# POWER.net
KiCad netlist of a schematic drawn in Altium Designer
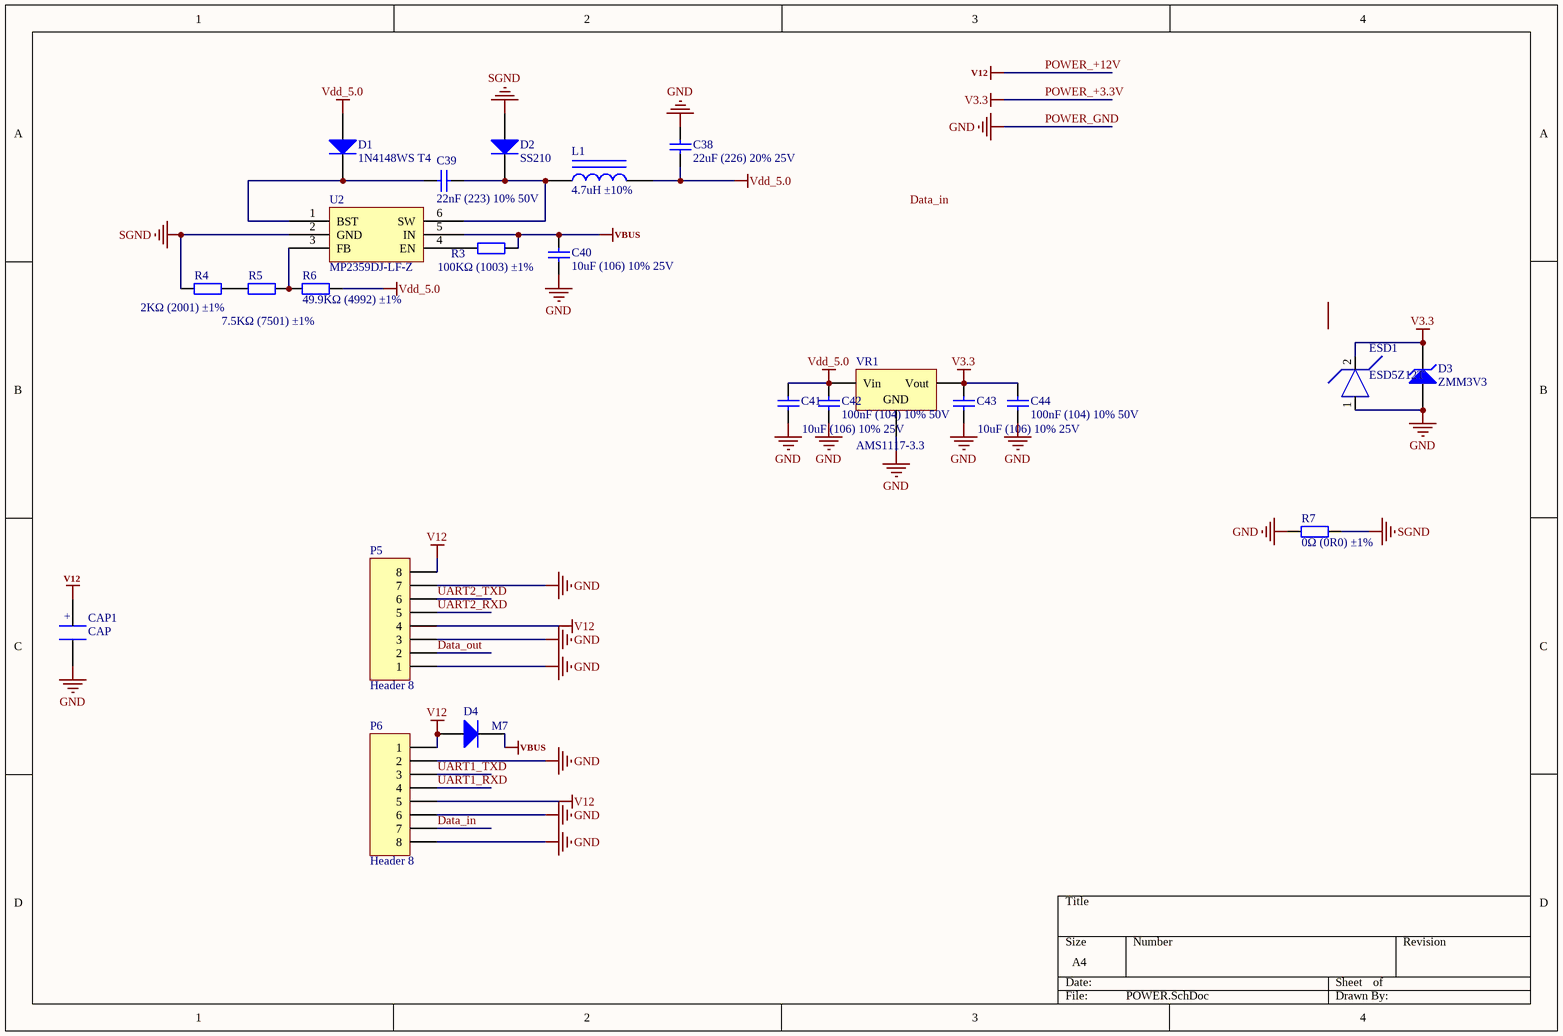
[diagram p0: POWER.SchDoc]

(export (version "E")
  (design (tool "Eeschema 10.0.6"))
  (components
    (comp (ref "C38")
      (value "22uF (226) 20% 25V")
      (footprint "0805_C")
      (description "贴片电容")
      (libsource (lib "Miscellaneous Devices LC") (part "0805 22uF (226) 20% 25V"))
    )
    (comp (ref "C39")
      (value "22nF (223) 10% 50V")
      (footprint "0603_C")
      (description "贴片电容")
      (libsource (lib "Miscellaneous Devices LC") (part "0603 22nF (223) 10% 50V"))
    )
    (comp (ref "C40")
      (value "10uF (106) 10% 25V")
      (footprint "0805_C")
      (description "贴片电容")
      (libsource (lib "Miscellaneous Devices LC") (part "0805 10uF (106) 10% 25V"))
    )
    (comp (ref "C41")
      (value "10uF (106) 10% 25V")
      (footprint "0805_C")
      (description "贴片电容")
      (libsource (lib "Miscellaneous Devices LC") (part "0805 10uF (106) 10% 25V"))
    )
    (comp (ref "C42")
      (value "100nF (104) 10% 50V")
      (footprint "0603_C")
      (description "贴片电容")
      (libsource (lib "Miscellaneous Devices LC") (part "0603 100nF (104) 10% 50V"))
    )
    (comp (ref "C43")
      (value "10uF (106) 10% 25V")
      (footprint "0805_C")
      (description "贴片电容")
      (libsource (lib "Miscellaneous Devices LC") (part "0805 10uF (106) 10% 25V"))
    )
    (comp (ref "C44")
      (value "100nF (104) 10% 50V")
      (footprint "0603_C")
      (description "贴片电容")
      (libsource (lib "Miscellaneous Devices LC") (part "0603 100nF (104) 10% 50V"))
    )
    (comp (ref "CAP1") (value "CAP") (footprint "8X12_CAP") (libsource (lib "mylib") (part "CAP")))
    (comp (ref "D1")
      (value "1N4148WS T4")
      (footprint "SOD-323")
      (description "二极管")
      (libsource (lib "Miscellaneous Devices LC") (part "SOD-323 1N4148WS T4"))
    )
    (comp (ref "D2")
      (value "SS210")
      (footprint "SMA(DO-214AC)_S1")
      (description "二极管")
      (libsource (lib "Miscellaneous Devices LC") (part "SMA(DO-214AC) SS210"))
    )
    (comp (ref "D3")
      (value "ZMM3V3")
      (footprint "LL-34")
      (description "稳压二极管")
      (libsource (lib "Miscellaneous Devices LC") (part "LL-34 ZMM3V3"))
    )
    (comp (ref "D4")
      (value "M7")
      (footprint "SMA(DO-214AC)_S1")
      (description "二极管")
      (libsource (lib "Miscellaneous Devices LC") (part "SMA(DO-214AC) M7"))
    )
    (comp (ref "ESD1") (value "ESD5Z12T") (footprint "SOD-523") (libsource (lib "mylib") (part "ESD-D")))
    (comp (ref "L1")
      (value "4.7uH ±10%")
      (footprint "L_4030")
      (description "贴片电感")
      (libsource (lib "Miscellaneous Devices LC") (part "0603 4.7uH 10%"))
    )
    (comp (ref "P5")
      (value "Header 8")
      (footprint "FPC1.0-2H-WS-8P")
      (description "Header, 8-Pin")
      (fields (field (name "PUBLISHER") "Altium Limited"))
      (libsource (lib "Miscellaneous Connectors") (part "Header 8"))
    )
    (comp (ref "P6")
      (value "Header 8")
      (footprint "FPC1.0-2H-WS-8P")
      (description "Header, 8-Pin")
      (fields (field (name "PUBLISHER") "Altium Limited"))
      (libsource (lib "") (part "Header 8_1"))
    )
    (comp (ref "R3")
      (value "100KΩ (1003) ±1%")
      (footprint "0603_R")
      (description "贴片电阻")
      (libsource (lib "Miscellaneous Devices LC") (part "0603 100KΩ (1003) 1%"))
    )
    (comp (ref "R4")
      (value "2KΩ (2001) ±1%")
      (footprint "0603_R")
      (description "贴片电阻")
      (libsource (lib "Miscellaneous Devices LC") (part "0603 2KΩ (2001) 1%"))
    )
    (comp (ref "R5")
      (value "7.5KΩ (7501) ±1%")
      (footprint "0603_R")
      (description "贴片电阻")
      (libsource (lib "Miscellaneous Devices LC") (part "0603 7.5KΩ (7501) 1%"))
    )
    (comp (ref "R6")
      (value "49.9KΩ (4992) ±1%")
      (footprint "0603_R")
      (description "贴片电阻")
      (libsource (lib "Miscellaneous Devices LC") (part "0603 49.9KΩ (4992) 1%"))
    )
    (comp (ref "R7")
      (value "0Ω (0R0) ±1%")
      (footprint "0603_R")
      (description "贴片电阻")
      (libsource (lib "Miscellaneous Devices LC") (part "0603 0Ω (0R0) 1%"))
    )
    (comp (ref "U2")
      (value "MP2359DJ-LF-Z")
      (footprint "SOT-23-6")
      (description "DC-DC芯片")
      (libsource (lib "Miscellaneous Devices LC") (part "MP2359DJ-LF-Z_[C14259]"))
    )
    (comp (ref "VR1")
      (value "AMS1117-3.3")
      (footprint "SOT-223")
      (description "低压差线性稳压(LDO)")
      (libsource (lib "Miscellaneous Devices LC") (part "SOT-223 AMS1117-3.3"))
    )
  )
  (nets
    (net (code "1") (name "/Data_in") (class "Default")
      (node (ref "P6") (pin "7") (pinfunction "7_7") (pintype "passive"))
    )
    (net (code "2") (name "/Data_out") (class "Default")
      (node (ref "P5") (pin "2") (pinfunction "2_2") (pintype "passive"))
    )
    (net (code "3") (name "/UART1_RXD") (class "Default")
      (node (ref "P6") (pin "4") (pinfunction "4_4") (pintype "passive"))
    )
    (net (code "4") (name "/UART1_TXD") (class "Default")
      (node (ref "P6") (pin "3") (pinfunction "3_3") (pintype "passive"))
    )
    (net (code "5") (name "/UART2_RXD") (class "Default")
      (node (ref "P5") (pin "5") (pinfunction "5_5") (pintype "passive"))
    )
    (net (code "6") (name "/UART2_TXD") (class "Default")
      (node (ref "P5") (pin "6") (pinfunction "6_6") (pintype "passive"))
    )
    (net (code "7") (name "GND") (class "Default")
      (node (ref "C38") (pin "2") (pinfunction "2_2") (pintype "passive"))
      (node (ref "C40") (pin "1") (pinfunction "1_1") (pintype "passive"))
      (node (ref "C41") (pin "1") (pinfunction "1_1") (pintype "passive"))
      (node (ref "C42") (pin "1") (pinfunction "1_1") (pintype "passive"))
      (node (ref "C43") (pin "1") (pinfunction "1_1") (pintype "passive"))
      (node (ref "C44") (pin "1") (pinfunction "1_1") (pintype "passive"))
      (node (ref "CAP1") (pin "2") (pinfunction "2_2") (pintype "passive"))
      (node (ref "D3") (pin "1") (pinfunction "A_1") (pintype "passive"))
      (node (ref "ESD1") (pin "1") (pinfunction "1_1") (pintype "passive"))
      (node (ref "P5") (pin "1") (pinfunction "1_1") (pintype "passive"))
      (node (ref "P5") (pin "3") (pinfunction "3_3") (pintype "passive"))
      (node (ref "P5") (pin "7") (pinfunction "7_7") (pintype "passive"))
      (node (ref "P6") (pin "2") (pinfunction "2_2") (pintype "passive"))
      (node (ref "P6") (pin "6") (pinfunction "6_6") (pintype "passive"))
      (node (ref "P6") (pin "8") (pinfunction "8_8") (pintype "passive"))
      (node (ref "R7") (pin "1") (pinfunction "1_1") (pintype "passive"))
      (node (ref "VR1") (pin "1") (pinfunction "GND_1") (pintype "passive"))
    )
    (net (code "8") (name "Net-(D1-K)") (class "Default")
      (node (ref "C39") (pin "1") (pinfunction "1_1") (pintype "passive"))
      (node (ref "D1") (pin "2") (pinfunction "K_2") (pintype "passive"))
      (node (ref "U2") (pin "1") (pinfunction "BST_1") (pintype "passive"))
    )
    (net (code "9") (name "Net-(D2-K)") (class "Default")
      (node (ref "C39") (pin "2") (pinfunction "2_2") (pintype "passive"))
      (node (ref "D2") (pin "2") (pinfunction "K_2") (pintype "passive"))
      (node (ref "L1") (pin "1") (pinfunction "1_1") (pintype "passive"))
      (node (ref "U2") (pin "6") (pinfunction "SW_6") (pintype "passive"))
    )
    (net (code "10") (name "Net-(R4-Pad1)") (class "Default")
      (node (ref "R4") (pin "1") (pinfunction "1_1") (pintype "passive"))
      (node (ref "R5") (pin "2") (pinfunction "2_2") (pintype "passive"))
    )
    (net (code "11") (name "Net-(U2-EN)") (class "Default")
      (node (ref "R3") (pin "1") (pinfunction "1_1") (pintype "passive"))
      (node (ref "U2") (pin "4") (pinfunction "EN_4") (pintype "passive"))
    )
    (net (code "12") (name "Net-(U2-FB)") (class "Default")
      (node (ref "R5") (pin "1") (pinfunction "1_1") (pintype "passive"))
      (node (ref "R6") (pin "1") (pinfunction "1_1") (pintype "passive"))
      (node (ref "U2") (pin "3") (pinfunction "FB_3") (pintype "passive"))
    )
    (net (code "13") (name "SGND") (class "Default")
      (node (ref "D2") (pin "1") (pinfunction "A_1") (pintype "passive"))
      (node (ref "R4") (pin "2") (pinfunction "2_2") (pintype "passive"))
      (node (ref "R7") (pin "2") (pinfunction "2_2") (pintype "passive"))
      (node (ref "U2") (pin "2") (pinfunction "GND_2") (pintype "passive"))
    )
    (net (code "14") (name "V3.3") (class "Default")
      (node (ref "C43") (pin "2") (pinfunction "2_2") (pintype "passive"))
      (node (ref "C44") (pin "2") (pinfunction "2_2") (pintype "passive"))
      (node (ref "D3") (pin "2") (pinfunction "K_2") (pintype "passive"))
      (node (ref "ESD1") (pin "2") (pinfunction "2_2") (pintype "passive"))
      (node (ref "VR1") (pin "2") (pinfunction "Vout_2") (pintype "passive"))
    )
    (net (code "15") (name "V12") (class "Default")
      (node (ref "CAP1") (pin "1") (pinfunction "1_1") (pintype "passive"))
      (node (ref "D4") (pin "1") (pinfunction "A_1") (pintype "passive"))
      (node (ref "P5") (pin "4") (pinfunction "4_4") (pintype "passive"))
      (node (ref "P5") (pin "8") (pinfunction "8_8") (pintype "passive"))
      (node (ref "P6") (pin "1") (pinfunction "1_1") (pintype "passive"))
      (node (ref "P6") (pin "5") (pinfunction "5_5") (pintype "passive"))
    )
    (net (code "16") (name "VBUS") (class "Default")
      (node (ref "C40") (pin "2") (pinfunction "2_2") (pintype "passive"))
      (node (ref "D4") (pin "2") (pinfunction "K_2") (pintype "passive"))
      (node (ref "R3") (pin "2") (pinfunction "2_2") (pintype "passive"))
      (node (ref "U2") (pin "5") (pinfunction "IN_5") (pintype "passive"))
    )
    (net (code "17") (name "Vdd_5.0") (class "Default")
      (node (ref "C38") (pin "1") (pinfunction "1_1") (pintype "passive"))
      (node (ref "C41") (pin "2") (pinfunction "2_2") (pintype "passive"))
      (node (ref "C42") (pin "2") (pinfunction "2_2") (pintype "passive"))
      (node (ref "D1") (pin "1") (pinfunction "A_1") (pintype "passive"))
      (node (ref "L1") (pin "2") (pinfunction "2_2") (pintype "passive"))
      (node (ref "R6") (pin "2") (pinfunction "2_2") (pintype "passive"))
      (node (ref "VR1") (pin "3") (pinfunction "Vin_3") (pintype "passive"))
    )
  )
)
